# Adafruit_Flora_LSM9DS0_9DoF.net
KiCad netlist of a schematic drawn in EAGLE
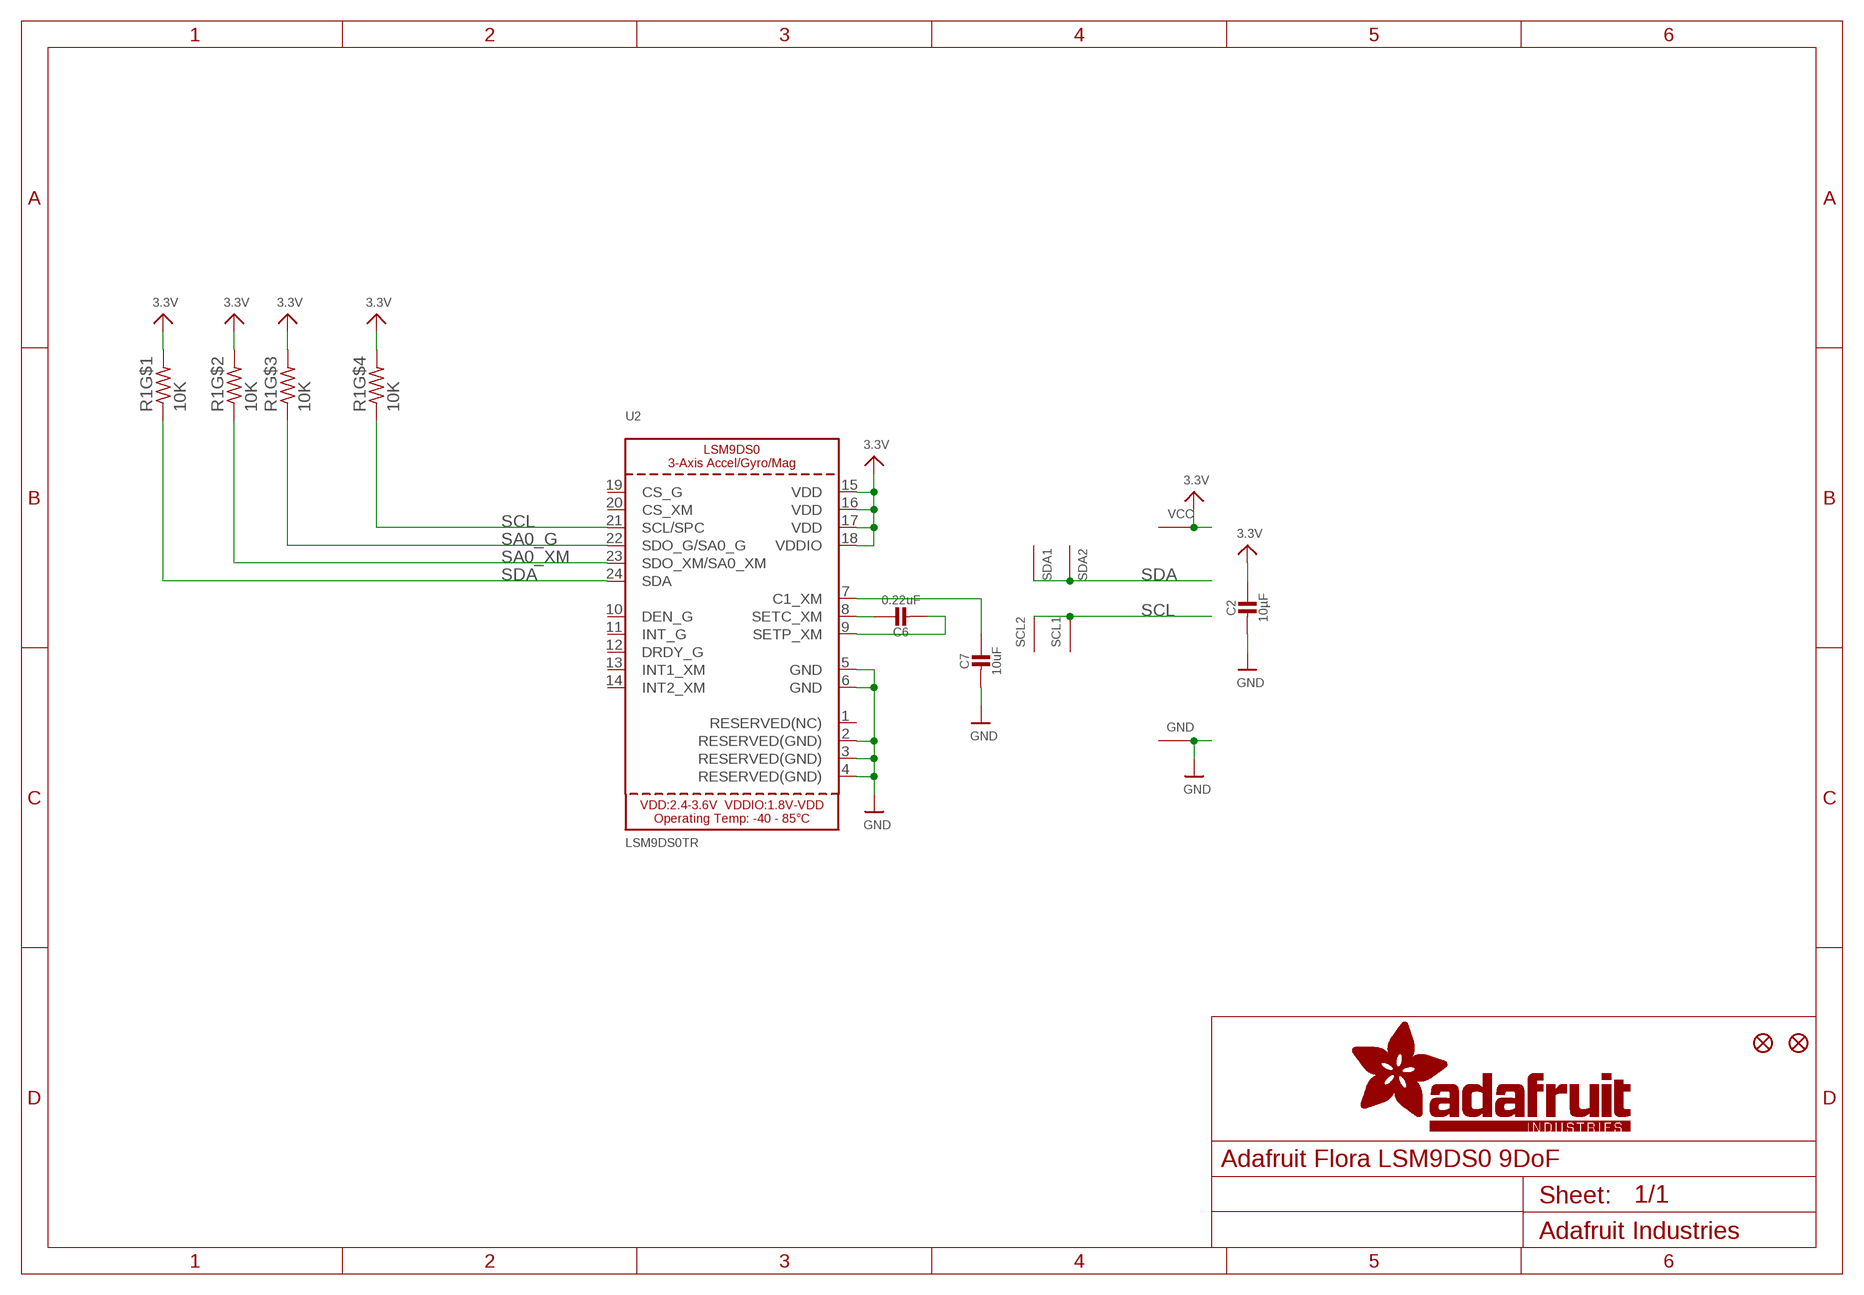
[diagram p0: schematic, sheet 1]

(export (version "E")
  (design (tool "Eeschema 10.0.6"))
  (components
    (comp (ref "C2")
      (value "10µF")
      (footprint "eagle-import:0805_10MGAP")
      (libsource (lib "eagle-import") (part "CAP_CERAMIC0805_10MGAP"))
    )
    (comp (ref "C6")
      (value "0.22uF")
      (footprint "eagle-import:0805-NO")
      (libsource (lib "eagle-import") (part "CAP_CERAMIC0805-NOOUTLINE"))
    )
    (comp (ref "C7")
      (value "10uF")
      (footprint "eagle-import:0805-NO")
      (libsource (lib "eagle-import") (part "CAP_CERAMIC0805-NOOUTLINE"))
    )
    (comp (ref "FID1")
      (value "FIDUCIAL\"\"")
      (footprint "eagle-import:FIDUCIAL_1MM")
      (libsource (lib "eagle-import") (part "FIDUCIAL{dblquote}{dblquote}"))
    )
    (comp (ref "FID2")
      (value "FIDUCIAL\"\"")
      (footprint "eagle-import:FIDUCIAL_1MM")
      (libsource (lib "eagle-import") (part "FIDUCIAL{dblquote}{dblquote}"))
    )
    (comp (ref "GND")
      (value "SEWTAP0.5IN")
      (footprint "eagle-import:SEWINGTAP_0.5")
      (libsource (lib "eagle-import") (part "SEWTAP0.5IN"))
    )
    (comp (ref "R1")
      (value "10K")
      (footprint "eagle-import:RESPACK_4X0603")
      (libsource (lib "eagle-import") (part "RESISTOR_4PACK_US"))
    )
    (comp (ref "SCL1")
      (value "SEWTAP0.5IN")
      (footprint "eagle-import:SEWINGTAP_0.5")
      (libsource (lib "eagle-import") (part "SEWTAP0.5IN"))
    )
    (comp (ref "SCL2")
      (value "SEWTAP0.5IN")
      (footprint "eagle-import:SEWINGTAP_0.5")
      (libsource (lib "eagle-import") (part "SEWTAP0.5IN"))
    )
    (comp (ref "SDA1")
      (value "SEWTAP0.5IN")
      (footprint "eagle-import:SEWINGTAP_0.5")
      (libsource (lib "eagle-import") (part "SEWTAP0.5IN"))
    )
    (comp (ref "SDA2")
      (value "SEWTAP0.5IN")
      (footprint "eagle-import:SEWINGTAP_0.5")
      (libsource (lib "eagle-import") (part "SEWTAP0.5IN"))
    )
    (comp (ref "U2")
      (value "LSM9DS0TR")
      (footprint "eagle-import:LGA24_4X4MM")
      (libsource (lib "eagle-import") (part "LSM9DS0"))
    )
    (comp (ref "VCC")
      (value "SEWTAP0.5IN")
      (footprint "eagle-import:SEWINGTAP_0.5")
      (libsource (lib "eagle-import") (part "SEWTAP0.5IN"))
    )
  )
  (nets
    (net (code "1") (name "/SA0_G") (class "Default")
      (node (ref "R1") (pin "3") (pinfunction "1_3") (pintype "passive"))
      (node (ref "U2") (pin "22") (pinfunction "SDO_G/SA0_G_22") (pintype "bidirectional"))
    )
    (net (code "2") (name "/SA0_XM") (class "Default")
      (node (ref "R1") (pin "2") (pinfunction "1_2") (pintype "passive"))
      (node (ref "U2") (pin "23") (pinfunction "SDO_XM/SA0_XM_23") (pintype "bidirectional"))
    )
    (net (code "3") (name "/SCL") (class "Default")
      (node (ref "R1") (pin "4") (pinfunction "1_4") (pintype "passive"))
      (node (ref "SCL1") (pin "TAP") (pinfunction "SEW_TAP") (pintype "bidirectional"))
      (node (ref "SCL2") (pin "TAP") (pinfunction "SEW_TAP") (pintype "bidirectional"))
      (node (ref "U2") (pin "21") (pinfunction "SCL/SPC_21") (pintype "bidirectional"))
    )
    (net (code "4") (name "/SDA") (class "Default")
      (node (ref "R1") (pin "1") (pinfunction "1_1") (pintype "passive"))
      (node (ref "SDA1") (pin "TAP") (pinfunction "SEW_TAP") (pintype "bidirectional"))
      (node (ref "SDA2") (pin "TAP") (pinfunction "SEW_TAP") (pintype "bidirectional"))
      (node (ref "U2") (pin "24") (pinfunction "SDA_24") (pintype "bidirectional"))
    )
    (net (code "5") (name "3.3V") (class "Default")
      (node (ref "C2") (pin "1") (pinfunction "1_1") (pintype "passive"))
      (node (ref "R1") (pin "5") (pinfunction "2_5") (pintype "passive"))
      (node (ref "R1") (pin "6") (pinfunction "2_6") (pintype "passive"))
      (node (ref "R1") (pin "7") (pinfunction "2_7") (pintype "passive"))
      (node (ref "R1") (pin "8") (pinfunction "2_8") (pintype "passive"))
      (node (ref "U2") (pin "15") (pinfunction "VDD_15") (pintype "power_in"))
      (node (ref "U2") (pin "16") (pinfunction "VDD_16") (pintype "power_in"))
      (node (ref "U2") (pin "17") (pinfunction "VDD_17") (pintype "power_in"))
      (node (ref "U2") (pin "18") (pinfunction "VDDIO_18") (pintype "power_in"))
      (node (ref "VCC") (pin "TAP") (pinfunction "SEW_TAP") (pintype "bidirectional"))
    )
    (net (code "6") (name "GND") (class "Default")
      (node (ref "C2") (pin "2") (pinfunction "2_2") (pintype "passive"))
      (node (ref "C7") (pin "2") (pinfunction "2_2") (pintype "passive"))
      (node (ref "GND") (pin "TAP") (pinfunction "SEW_TAP") (pintype "bidirectional"))
      (node (ref "U2") (pin "2") (pinfunction "RESERVED(GND)_2") (pintype "power_in"))
      (node (ref "U2") (pin "3") (pinfunction "RESERVED(GND)_3") (pintype "power_in"))
      (node (ref "U2") (pin "4") (pinfunction "RESERVED(GND)_4") (pintype "power_in"))
      (node (ref "U2") (pin "5") (pinfunction "GND_5") (pintype "power_in"))
      (node (ref "U2") (pin "6") (pinfunction "GND_6") (pintype "power_in"))
    )
    (net (code "7") (name "Net-(U2-C1_XM)") (class "Default")
      (node (ref "C7") (pin "1") (pinfunction "1_1") (pintype "passive"))
      (node (ref "U2") (pin "7") (pinfunction "C1_XM_7") (pintype "bidirectional"))
    )
    (net (code "8") (name "Net-(U2-SETC_XM)") (class "Default")
      (node (ref "C6") (pin "1") (pinfunction "1_1") (pintype "passive"))
      (node (ref "U2") (pin "8") (pinfunction "SETC_XM_8") (pintype "bidirectional"))
    )
    (net (code "9") (name "Net-(U2-SETP_XM)") (class "Default")
      (node (ref "C6") (pin "2") (pinfunction "2_2") (pintype "passive"))
      (node (ref "U2") (pin "9") (pinfunction "SETP_XM_9") (pintype "bidirectional"))
    )
    (net (code "10") (name "unconnected-(U2-CS_G-Pad19)") (class "Default")
      (node (ref "U2") (pin "19") (pinfunction "CS_G_19") (pintype "bidirectional"))
    )
    (net (code "11") (name "unconnected-(U2-CS_XM-Pad20)") (class "Default")
      (node (ref "U2") (pin "20") (pinfunction "CS_XM_20") (pintype "bidirectional"))
    )
    (net (code "12") (name "unconnected-(U2-DEN_G-Pad10)") (class "Default")
      (node (ref "U2") (pin "10") (pinfunction "DEN_G_10") (pintype "bidirectional"))
    )
    (net (code "13") (name "unconnected-(U2-DRDY_G-Pad12)") (class "Default")
      (node (ref "U2") (pin "12") (pinfunction "DRDY_G_12") (pintype "bidirectional"))
    )
    (net (code "14") (name "unconnected-(U2-INT1_XM-Pad13)") (class "Default")
      (node (ref "U2") (pin "13") (pinfunction "INT1_XM_13") (pintype "bidirectional"))
    )
    (net (code "15") (name "unconnected-(U2-INT2_XM-Pad14)") (class "Default")
      (node (ref "U2") (pin "14") (pinfunction "INT2_XM_14") (pintype "bidirectional"))
    )
    (net (code "16") (name "unconnected-(U2-INT_G-Pad11)") (class "Default")
      (node (ref "U2") (pin "11") (pinfunction "INT_G_11") (pintype "bidirectional"))
    )
    (net (code "17") (name "unconnected-(U2-RESERVED(NC)-Pad1)") (class "Default")
      (node (ref "U2") (pin "1") (pinfunction "RESERVED(NC)_1") (pintype "no_connect"))
    )
  )
)
